# LPCB235_-_IMU.net
KiCad netlist of a schematic drawn in Altium Designer
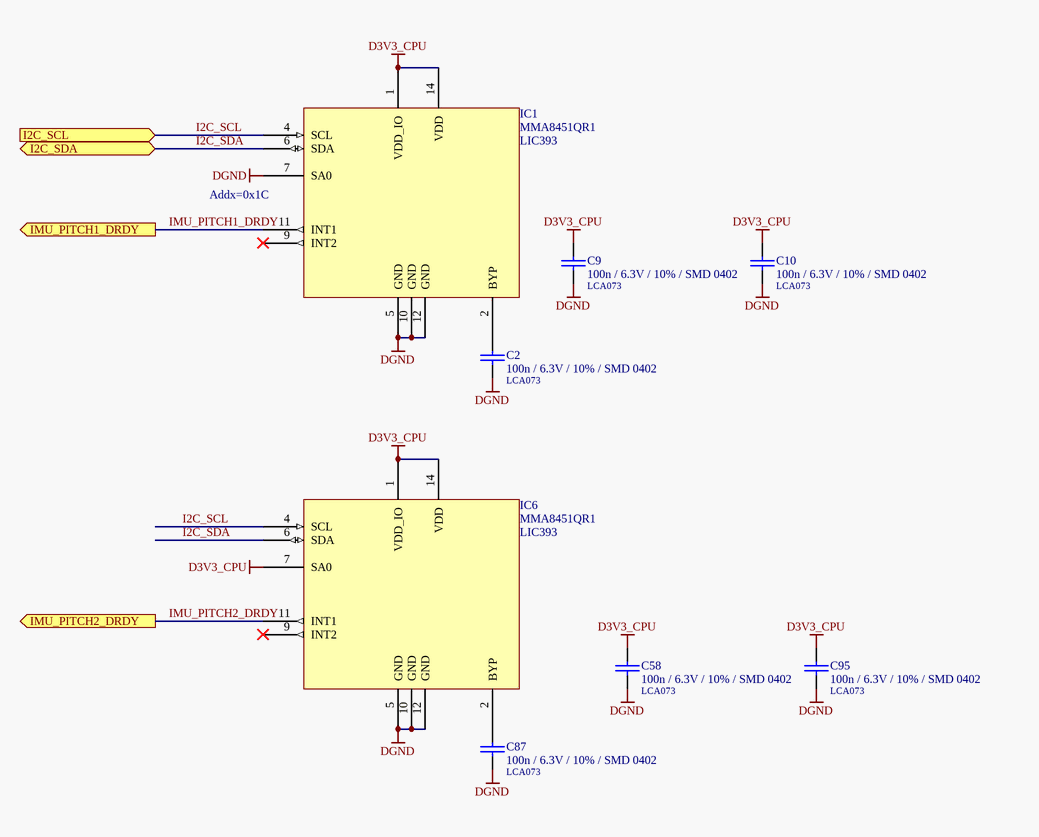
[diagram p0: LPCB235 - IMU.SchDoc]

(export (version "E")
  (design (tool "Eeschema 10.0.6"))
  (components
    (comp (ref "C2")
      (value "100n / 6.3V / 10% / SMD 0402")
      (footprint "LFP012__CC1005-0402-IPC7351_B")
      (description "Capacitor, Ceramic Chip, 100nF (0.1uF), 6.3V, 10%, SMD 0402 [LCA073]")
      (fields (field (name "LDL_NUMBER") "LCA073"))
      (libsource (lib "LDL_Capacitors") (part "100n / 6.3V / 10% / SMD 0402"))
    )
    (comp (ref "C9")
      (value "100n / 6.3V / 10% / SMD 0402")
      (footprint "LFP012__CC1005-0402-IPC7351_B")
      (description "Capacitor, Ceramic Chip, 100nF (0.1uF), 6.3V, 10%, SMD 0402 [LCA073]")
      (fields (field (name "LDL_NUMBER") "LCA073"))
      (libsource (lib "LDL_Capacitors") (part "100n / 6.3V / 10% / SMD 0402"))
    )
    (comp (ref "C10")
      (value "100n / 6.3V / 10% / SMD 0402")
      (footprint "LFP012__CC1005-0402-IPC7351_B")
      (description "Capacitor, Ceramic Chip, 100nF (0.1uF), 6.3V, 10%, SMD 0402 [LCA073]")
      (fields (field (name "LDL_NUMBER") "LCA073"))
      (libsource (lib "LDL_Capacitors") (part "100n / 6.3V / 10% / SMD 0402"))
    )
    (comp (ref "C58")
      (value "100n / 6.3V / 10% / SMD 0402")
      (footprint "LFP012__CC1005-0402-IPC7351_B")
      (description "Capacitor, Ceramic Chip, 100nF (0.1uF), 6.3V, 10%, SMD 0402 [LCA073]")
      (fields (field (name "LDL_NUMBER") "LCA073"))
      (libsource (lib "LDL_Capacitors") (part "100n / 6.3V / 10% / SMD 0402"))
    )
    (comp (ref "C87")
      (value "100n / 6.3V / 10% / SMD 0402")
      (footprint "LFP012__CC1005-0402-IPC7351_B")
      (description "Capacitor, Ceramic Chip, 100nF (0.1uF), 6.3V, 10%, SMD 0402 [LCA073]")
      (fields (field (name "LDL_NUMBER") "LCA073"))
      (libsource (lib "LDL_Capacitors") (part "100n / 6.3V / 10% / SMD 0402"))
    )
    (comp (ref "C95")
      (value "100n / 6.3V / 10% / SMD 0402")
      (footprint "LFP012__CC1005-0402-IPC7351_B")
      (description "Capacitor, Ceramic Chip, 100nF (0.1uF), 6.3V, 10%, SMD 0402 [LCA073]")
      (fields (field (name "LDL_NUMBER") "LCA073"))
      (libsource (lib "LDL_Capacitors") (part "100n / 6.3V / 10% / SMD 0402"))
    )
    (comp (ref "IC1")
      (value "MMA8451QR1")
      (footprint "LFP051__QFN16")
      (description "IC, Accelerometer, 3-Axis, 3.3V, I2C, SMD QFN16 [LIC393]")
      (fields (field (name "LDL_NUMBER") "LIC393"))
      (libsource (lib "LDL_Semiconductors") (part "MMA8451QR1"))
    )
    (comp (ref "IC6")
      (value "MMA8451QR1")
      (footprint "LFP051__QFN16")
      (description "IC, Accelerometer, 3-Axis, 3.3V, I2C, SMD QFN16 [LIC393]")
      (fields (field (name "LDL_NUMBER") "LIC393"))
      (libsource (lib "LDL_Semiconductors") (part "MMA8451QR1"))
    )
  )
  (nets
    (net (code "1") (name "/I2C_SCL") (class "Default")
      (node (ref "IC1") (pin "4") (pinfunction "SCL_4") (pintype "input"))
      (node (ref "IC6") (pin "4") (pinfunction "SCL_4") (pintype "input"))
    )
    (net (code "2") (name "/I2C_SDA") (class "Default")
      (node (ref "IC1") (pin "6") (pinfunction "SDA_6") (pintype "bidirectional"))
      (node (ref "IC6") (pin "6") (pinfunction "SDA_6") (pintype "bidirectional"))
    )
    (net (code "3") (name "/IMU_PITCH1_DRDY") (class "Default")
      (node (ref "IC1") (pin "11") (pinfunction "INT1_11") (pintype "output"))
    )
    (net (code "4") (name "/IMU_PITCH2_DRDY") (class "Default")
      (node (ref "IC6") (pin "11") (pinfunction "INT1_11") (pintype "output"))
    )
    (net (code "5") (name "D3V3_CPU") (class "Default")
      (node (ref "C10") (pin "1") (pintype "passive"))
      (node (ref "C58") (pin "1") (pintype "passive"))
      (node (ref "C9") (pin "1") (pintype "passive"))
      (node (ref "C95") (pin "1") (pintype "passive"))
      (node (ref "IC1") (pin "1") (pinfunction "VDD_IO_1") (pintype "power_in"))
      (node (ref "IC1") (pin "14") (pinfunction "VDD_14") (pintype "power_in"))
      (node (ref "IC6") (pin "1") (pinfunction "VDD_IO_1") (pintype "power_in"))
      (node (ref "IC6") (pin "14") (pinfunction "VDD_14") (pintype "power_in"))
      (node (ref "IC6") (pin "7") (pinfunction "SA0_7") (pintype "passive"))
    )
    (net (code "6") (name "DGND") (class "Default")
      (node (ref "C10") (pin "2") (pintype "passive"))
      (node (ref "C2") (pin "2") (pintype "passive"))
      (node (ref "C58") (pin "2") (pintype "passive"))
      (node (ref "C87") (pin "2") (pintype "passive"))
      (node (ref "C9") (pin "2") (pintype "passive"))
      (node (ref "C95") (pin "2") (pintype "passive"))
      (node (ref "IC1") (pin "10") (pinfunction "GND_10") (pintype "power_in"))
      (node (ref "IC1") (pin "12") (pinfunction "GND_12") (pintype "power_in"))
      (node (ref "IC1") (pin "5") (pinfunction "GND_5") (pintype "power_in"))
      (node (ref "IC1") (pin "7") (pinfunction "SA0_7") (pintype "passive"))
      (node (ref "IC6") (pin "10") (pinfunction "GND_10") (pintype "power_in"))
      (node (ref "IC6") (pin "12") (pinfunction "GND_12") (pintype "power_in"))
      (node (ref "IC6") (pin "5") (pinfunction "GND_5") (pintype "power_in"))
    )
    (net (code "7") (name "Net-(IC1-BYP)") (class "Default")
      (node (ref "C2") (pin "1") (pintype "passive"))
      (node (ref "IC1") (pin "2") (pinfunction "BYP_2") (pintype "passive"))
    )
    (net (code "8") (name "Net-(IC6-BYP)") (class "Default")
      (node (ref "C87") (pin "1") (pintype "passive"))
      (node (ref "IC6") (pin "2") (pinfunction "BYP_2") (pintype "passive"))
    )
    (net (code "9") (name "unconnected-(IC1-INT2-Pad9)") (class "Default")
      (node (ref "IC1") (pin "9") (pinfunction "INT2_9") (pintype "output+no_connect"))
    )
    (net (code "10") (name "unconnected-(IC6-INT2-Pad9)") (class "Default")
      (node (ref "IC6") (pin "9") (pinfunction "INT2_9") (pintype "output+no_connect"))
    )
  )
)
